# proiect.net
KiCad netlist of a schematic drawn in EAGLE
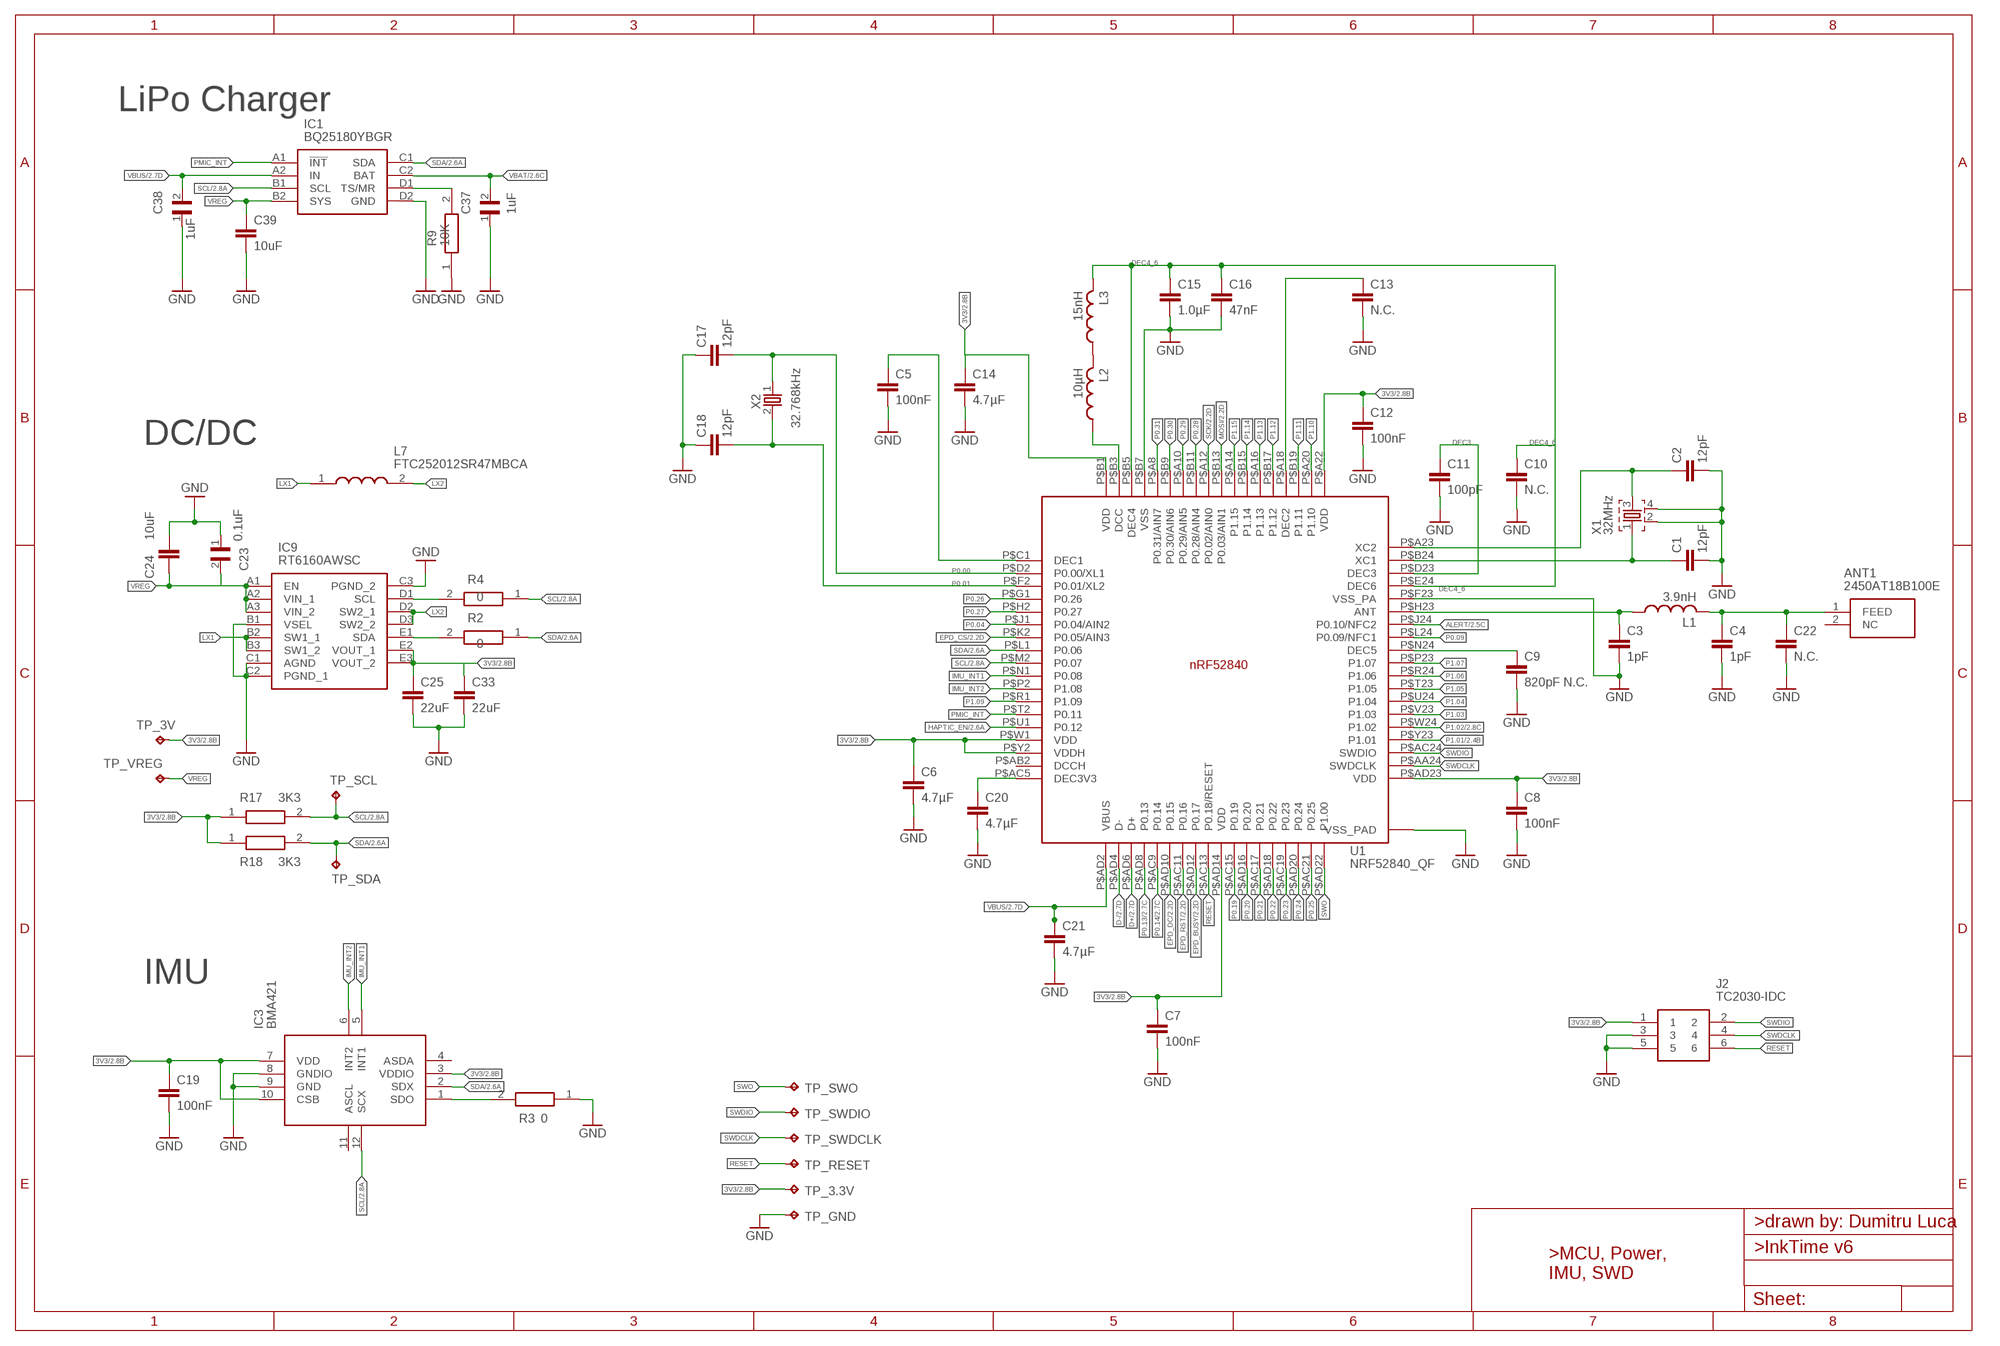
[diagram p0: schematic, sheet 1]
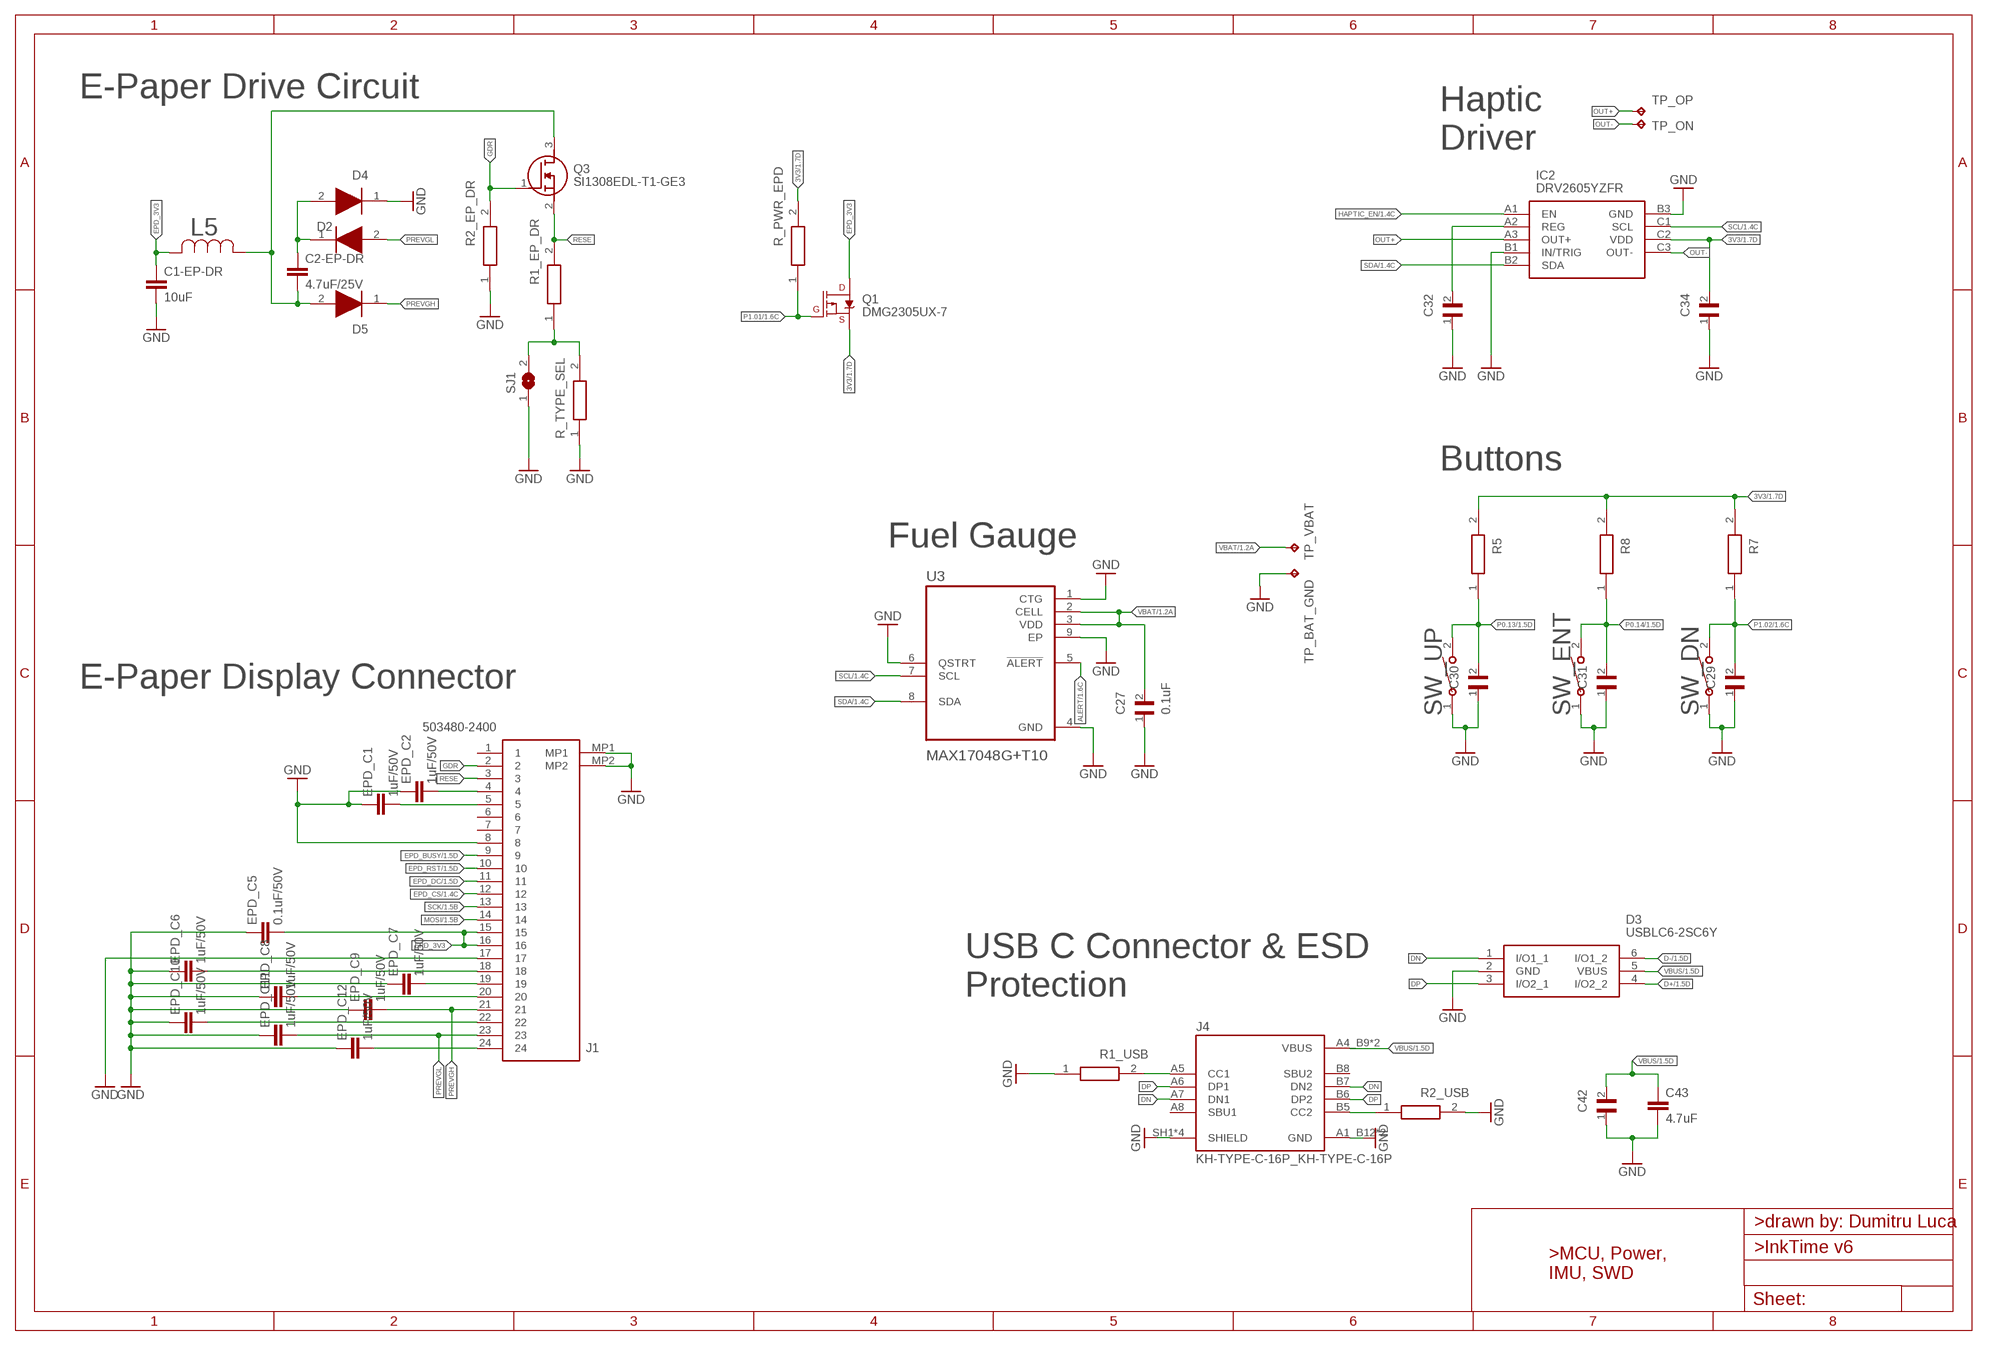
[diagram p1: schematic, sheet 2]

(export (version "E")
  (design (tool "Eeschema 10.0.6"))
  (components
    (comp (ref "ANT1")
      (value "2450AT18B100E")
      (footprint "eagle-import:2450AT18B100E_ANTC3216X140N")
      (fields (field (name "MOUSER_PART_NUMBER") "609-2450AT18B100E"))
      (libsource (lib "eagle-import") (part "2450AT18B100E_2450AT18B100E"))
    )
    (comp (ref "C1")
      (value "12pF")
      (footprint "eagle-import:NORDIC_NRF_3_RESC0201_L")
      (libsource (lib "eagle-import") (part "NORDIC_NRF_3_CAPACITOR_0201_L"))
    )
    (comp (ref "C2")
      (value "12pF")
      (footprint "eagle-import:NORDIC_NRF_3_RESC0201_L")
      (libsource (lib "eagle-import") (part "NORDIC_NRF_3_CAPACITOR_0201_L"))
    )
    (comp (ref "C3")
      (value "1pF")
      (footprint "eagle-import:NORDIC_NRF_3_RESC0201_L")
      (libsource (lib "eagle-import") (part "NORDIC_NRF_3_CAPACITOR_0201_L"))
    )
    (comp (ref "C4")
      (value "1pF")
      (footprint "eagle-import:NORDIC_NRF_3_RESC0201_L")
      (libsource (lib "eagle-import") (part "NORDIC_NRF_3_CAPACITOR_0201_L"))
    )
    (comp (ref "C5")
      (value "100nF")
      (footprint "eagle-import:NORDIC_NRF_3_RESC0201_L")
      (libsource (lib "eagle-import") (part "NORDIC_NRF_3_CAPACITOR_0201_L"))
    )
    (comp (ref "C6")
      (value "4.7µF")
      (footprint "eagle-import:NORDIC_NRF_3_RESC0201_L")
      (libsource (lib "eagle-import") (part "NORDIC_NRF_3_CAPACITOR_0201_L"))
    )
    (comp (ref "C7")
      (value "100nF")
      (footprint "eagle-import:NORDIC_NRF_3_RESC0201_L")
      (libsource (lib "eagle-import") (part "NORDIC_NRF_3_CAPACITOR_0201_L"))
    )
    (comp (ref "C8")
      (value "100nF")
      (footprint "eagle-import:NORDIC_NRF_3_RESC0201_L")
      (libsource (lib "eagle-import") (part "NORDIC_NRF_3_CAPACITOR_0201_L"))
    )
    (comp (ref "C9")
      (value "820pF N.C.")
      (footprint "eagle-import:NORDIC_NRF_3_RESC0201_L")
      (libsource (lib "eagle-import") (part "NORDIC_NRF_3_CAPACITOR_0201_L"))
    )
    (comp (ref "C10")
      (value "N.C.")
      (footprint "eagle-import:NORDIC_NRF_3_RESC0201_L")
      (libsource (lib "eagle-import") (part "NORDIC_NRF_3_CAPACITOR_0201_L"))
    )
    (comp (ref "C11")
      (value "100pF")
      (footprint "eagle-import:NORDIC_NRF_3_RESC0201_L")
      (libsource (lib "eagle-import") (part "NORDIC_NRF_3_CAPACITOR_0201_L"))
    )
    (comp (ref "C12")
      (value "100nF")
      (footprint "eagle-import:NORDIC_NRF_3_RESC0201_L")
      (libsource (lib "eagle-import") (part "NORDIC_NRF_3_CAPACITOR_0201_L"))
    )
    (comp (ref "C13")
      (value "N.C.")
      (footprint "eagle-import:NORDIC_NRF_3_RESC0201_L")
      (libsource (lib "eagle-import") (part "NORDIC_NRF_3_CAPACITOR_0201_L"))
    )
    (comp (ref "C14")
      (value "4.7µF")
      (footprint "eagle-import:NORDIC_NRF_3_RESC0201_L")
      (libsource (lib "eagle-import") (part "NORDIC_NRF_3_CAPACITOR_0201_L"))
    )
    (comp (ref "C15")
      (value "1.0µF")
      (footprint "eagle-import:NORDIC_NRF_3_RESC0201_L")
      (libsource (lib "eagle-import") (part "NORDIC_NRF_3_CAPACITOR_0201_L"))
    )
    (comp (ref "C16")
      (value "47nF")
      (footprint "eagle-import:NORDIC_NRF_3_RESC0201_L")
      (libsource (lib "eagle-import") (part "NORDIC_NRF_3_CAPACITOR_0201_L"))
    )
    (comp (ref "C17")
      (value "12pF")
      (footprint "eagle-import:NORDIC_NRF_3_RESC0201_L")
      (libsource (lib "eagle-import") (part "NORDIC_NRF_3_CAPACITOR_0201_L"))
    )
    (comp (ref "C18")
      (value "12pF")
      (footprint "eagle-import:NORDIC_NRF_3_RESC0201_L")
      (libsource (lib "eagle-import") (part "NORDIC_NRF_3_CAPACITOR_0201_L"))
    )
    (comp (ref "C19")
      (value "100nF")
      (footprint "eagle-import:NORDIC_NRF_3_RESC0201_L")
      (libsource (lib "eagle-import") (part "NORDIC_NRF_3_CAPACITOR_0201_L"))
    )
    (comp (ref "C20")
      (value "4.7µF")
      (footprint "eagle-import:NORDIC_NRF_3_RESC0201_L")
      (libsource (lib "eagle-import") (part "NORDIC_NRF_3_CAPACITOR_0201_L"))
    )
    (comp (ref "C21")
      (value "4.7µF")
      (footprint "eagle-import:NORDIC_NRF_3_RESC0201_L")
      (libsource (lib "eagle-import") (part "NORDIC_NRF_3_CAPACITOR_0201_L"))
    )
    (comp (ref "C22")
      (value "N.C.")
      (footprint "eagle-import:NORDIC_NRF_3_RESC0201_L")
      (libsource (lib "eagle-import") (part "NORDIC_NRF_3_CAPACITOR_0201_L"))
    )
    (comp (ref "C23")
      (value "0.1uF")
      (footprint "eagle-import:GRM011R60J152KE01L_1_0201")
      (libsource (lib "eagle-import") (part "GRM011R60J152KE01L_1_GRM011R60J152KE01L"))
    )
    (comp (ref "C24")
      (value "10uF")
      (footprint "eagle-import:NORDIC_NRF_3_RESC0201_L")
      (libsource (lib "eagle-import") (part "NORDIC_NRF_3_CAPACITOR_0201_L"))
    )
    (comp (ref "C25")
      (value "22uF")
      (footprint "eagle-import:NORDIC_NRF_3_RESC0201_L")
      (libsource (lib "eagle-import") (part "NORDIC_NRF_3_CAPACITOR_0201_L"))
    )
    (comp (ref "C33")
      (value "22uF")
      (footprint "eagle-import:NORDIC_NRF_3_RESC0201_L")
      (libsource (lib "eagle-import") (part "NORDIC_NRF_3_CAPACITOR_0201_L"))
    )
    (comp (ref "C37")
      (value "1uF")
      (footprint "eagle-import:GRM011R60J152KE01L_1_0201")
      (libsource (lib "eagle-import") (part "GRM011R60J152KE01L_1_GRM011R60J152KE01L"))
    )
    (comp (ref "C38")
      (value "1uF")
      (footprint "eagle-import:GRM011R60J152KE01L_1_0201")
      (libsource (lib "eagle-import") (part "GRM011R60J152KE01L_1_GRM011R60J152KE01L"))
    )
    (comp (ref "C39")
      (value "10uF")
      (footprint "eagle-import:NORDIC_NRF_3_RESC0201_L")
      (libsource (lib "eagle-import") (part "NORDIC_NRF_3_CAPACITOR_0201_L"))
    )
    (comp (ref "IC1")
      (value "BQ25180YBGR")
      (footprint "eagle-import:BQ25180YBGR_BGA8C40P2X4_100X155X50")
      (fields (field (name "MOUSER_PART_NUMBER") "595-BQ25180YBGR"))
      (libsource (lib "eagle-import") (part "BQ25180YBGR_BQ25180YBGR"))
    )
    (comp (ref "IC3")
      (value "BMA421")
      (footprint "eagle-import:BMA423_BMA423")
      (fields (field (name "ARROW_PART_NUMBER") "BMA423") (field (name "MOUSER_PART_NUMBER") "262-BMA423"))
      (libsource (lib "eagle-import") (part "BMA423_BMA423"))
    )
    (comp (ref "IC9")
      (value "RT6160AWSC")
      (footprint "eagle-import:RT6160AWSC_BGA15C40P3X5_140X230X60")
      (fields (field (name "MOUSER_PART_NUMBER") "835-RT6160AWSC"))
      (libsource (lib "eagle-import") (part "RT6160AWSC_RT6160AWSC"))
    )
    (comp (ref "J2")
      (value "TC2030-IDC")
      (footprint "eagle-import:TC2030-IDC_TC2030IDC")
      (libsource (lib "eagle-import") (part "TC2030-IDC_TC2030-IDC"))
    )
    (comp (ref "L1")
      (value "3.9nH")
      (footprint "eagle-import:NORDIC_NRF_2_RESC0402_L")
      (libsource (lib "eagle-import") (part "NORDIC_NRF_2_INDUCTOR_0402_L"))
    )
    (comp (ref "L2")
      (value "10µH")
      (footprint "eagle-import:NORDIC_NRF_2_RESC0402_L")
      (libsource (lib "eagle-import") (part "NORDIC_NRF_2_INDUCTOR_0402_L"))
    )
    (comp (ref "L3")
      (value "15nH")
      (footprint "eagle-import:NORDIC_NRF_2_RESC0402_L")
      (libsource (lib "eagle-import") (part "NORDIC_NRF_2_INDUCTOR_0402_L"))
    )
    (comp (ref "L7")
      (value "FTC252012SR47MBCA")
      (footprint "eagle-import:MLP2016SR47MT0S1_INDC2016X100N")
      (libsource (lib "eagle-import") (part "MLP2016SR47MT0S1_FTC252012SR47MBCA"))
    )
    (comp (ref "R2")
      (value "0")
      (footprint "eagle-import:CPF0201D7K68C1_0201")
      (libsource (lib "eagle-import") (part "CPF0201D7K68C1_CPF0201D7K68C1"))
    )
    (comp (ref "R3")
      (value "0")
      (footprint "eagle-import:CPF0201D7K68C1_0201")
      (libsource (lib "eagle-import") (part "CPF0201D7K68C1_CPF0201D7K68C1"))
    )
    (comp (ref "R4")
      (value "0")
      (footprint "eagle-import:CPF0201D7K68C1_0201")
      (libsource (lib "eagle-import") (part "CPF0201D7K68C1_CPF0201D7K68C1"))
    )
    (comp (ref "R9")
      (value "10K")
      (footprint "eagle-import:CPF0201D7K68C1_0201")
      (libsource (lib "eagle-import") (part "CPF0201D7K68C1_CPF0201D7K68C1"))
    )
    (comp (ref "R17")
      (value "3K3")
      (footprint "eagle-import:CPF0201D7K68C1_0201")
      (libsource (lib "eagle-import") (part "CPF0201D7K68C1_CPF0201D7K68C1"))
    )
    (comp (ref "R18")
      (value "3K3")
      (footprint "eagle-import:CPF0201D7K68C1_0201")
      (libsource (lib "eagle-import") (part "CPF0201D7K68C1_CPF0201D7K68C1"))
    )
    (comp (ref "TP_3.3V")
      (value "HECTOR_WATCH_1_TPTP20R")
      (footprint "eagle-import:HECTOR_WATCH_1_TP20R")
      (libsource (lib "eagle-import") (part "HECTOR_WATCH_1_TPTP20R"))
    )
    (comp (ref "TP_3V")
      (value "HECTOR_WATCH_1_TPTP20R")
      (footprint "eagle-import:HECTOR_WATCH_1_TP20R")
      (libsource (lib "eagle-import") (part "HECTOR_WATCH_1_TPTP20R"))
    )
    (comp (ref "TP_GND")
      (value "HECTOR_WATCH_1_TPTP20R")
      (footprint "eagle-import:HECTOR_WATCH_1_TP20R")
      (libsource (lib "eagle-import") (part "HECTOR_WATCH_1_TPTP20R"))
    )
    (comp (ref "TP_RESET")
      (value "HECTOR_WATCH_1_TPTP20R")
      (footprint "eagle-import:HECTOR_WATCH_1_TP20R")
      (libsource (lib "eagle-import") (part "HECTOR_WATCH_1_TPTP20R"))
    )
    (comp (ref "TP_SCL")
      (value "HECTOR_WATCH_1_TPTP20R")
      (footprint "eagle-import:HECTOR_WATCH_1_TP20R")
      (libsource (lib "eagle-import") (part "HECTOR_WATCH_1_TPTP20R"))
    )
    (comp (ref "TP_SDA")
      (value "HECTOR_WATCH_1_TPTP20R")
      (footprint "eagle-import:HECTOR_WATCH_1_TP20R")
      (libsource (lib "eagle-import") (part "HECTOR_WATCH_1_TPTP20R"))
    )
    (comp (ref "TP_SWDCLK")
      (value "HECTOR_WATCH_1_TPTP20R")
      (footprint "eagle-import:HECTOR_WATCH_1_TP20R")
      (libsource (lib "eagle-import") (part "HECTOR_WATCH_1_TPTP20R"))
    )
    (comp (ref "TP_SWDIO")
      (value "HECTOR_WATCH_1_TPTP20R")
      (footprint "eagle-import:HECTOR_WATCH_1_TP20R")
      (libsource (lib "eagle-import") (part "HECTOR_WATCH_1_TPTP20R"))
    )
    (comp (ref "TP_SWO")
      (value "HECTOR_WATCH_1_TPTP20R")
      (footprint "eagle-import:HECTOR_WATCH_1_TP20R")
      (libsource (lib "eagle-import") (part "HECTOR_WATCH_1_TPTP20R"))
    )
    (comp (ref "TP_VREG")
      (value "HECTOR_WATCH_1_TPTP20R")
      (footprint "eagle-import:HECTOR_WATCH_1_TP20R")
      (libsource (lib "eagle-import") (part "HECTOR_WATCH_1_TPTP20R"))
    )
    (comp (ref "U1")
      (value "NRF52840_QF")
      (footprint "eagle-import:NORDIC_NRF_4_AQFN50P700X700X85_HS-74N")
      (libsource (lib "eagle-import") (part "NORDIC_NRF_4_NRF52840_QF"))
    )
    (comp (ref "X1")
      (value "32MHz")
      (footprint "eagle-import:NORDIC_NRF_BT-XTAL_2016_N")
      (libsource (lib "eagle-import") (part "NORDIC_NRF_XTAL_32MHZ"))
    )
    (comp (ref "X2")
      (value "32.768kHz")
      (footprint "eagle-import:NORDIC_NRF_1_XTAL_3215_N")
      (libsource (lib "eagle-import") (part "NORDIC_NRF_1_XTAL_32KHZ"))
    )
    (comp (ref "C1-EP-DR")
      (value "10uF")
      (footprint "eagle-import:NORDIC_NRF_3_RESC0201_L")
      (libsource (lib "eagle-import") (part "NORDIC_NRF_3_CAPACITOR_0201_L"))
    )
    (comp (ref "C2-EP-DR")
      (value "4.7uF/25V")
      (footprint "eagle-import:NORDIC_NRF_3_RESC0201_L")
      (libsource (lib "eagle-import") (part "NORDIC_NRF_3_CAPACITOR_0201_L"))
    )
    (comp (ref "C27")
      (value "0.1uF")
      (footprint "eagle-import:GRM011R60J152KE01L_1_0201")
      (libsource (lib "eagle-import") (part "GRM011R60J152KE01L_1_GRM011R60J152KE01L"))
    )
    (comp (ref "C29")
      (value "1uF")
      (footprint "eagle-import:GRM011R60J152KE01L_1_0201")
      (libsource (lib "eagle-import") (part "GRM011R60J152KE01L_1_GRM011R60J152KE01L"))
    )
    (comp (ref "C30")
      (value "1uF")
      (footprint "eagle-import:GRM011R60J152KE01L_1_0201")
      (libsource (lib "eagle-import") (part "GRM011R60J152KE01L_1_GRM011R60J152KE01L"))
    )
    (comp (ref "C31")
      (value "1uF")
      (footprint "eagle-import:GRM011R60J152KE01L_1_0201")
      (libsource (lib "eagle-import") (part "GRM011R60J152KE01L_1_GRM011R60J152KE01L"))
    )
    (comp (ref "C32")
      (value "1uF")
      (footprint "eagle-import:GRM011R60J152KE01L_1_0201")
      (libsource (lib "eagle-import") (part "GRM011R60J152KE01L_1_GRM011R60J152KE01L"))
    )
    (comp (ref "C34")
      (value "0.1uF")
      (footprint "eagle-import:GRM011R60J152KE01L_1_0201")
      (libsource (lib "eagle-import") (part "GRM011R60J152KE01L_1_GRM011R60J152KE01L"))
    )
    (comp (ref "C42")
      (value "0.1uF")
      (footprint "eagle-import:GRM011R60J152KE01L_1_0201")
      (libsource (lib "eagle-import") (part "GRM011R60J152KE01L_1_GRM011R60J152KE01L"))
    )
    (comp (ref "C43")
      (value "4.7uF")
      (footprint "eagle-import:NORDIC_NRF_3_RESC0201_L")
      (libsource (lib "eagle-import") (part "NORDIC_NRF_3_CAPACITOR_0201_L"))
    )
    (comp (ref "D2")
      (value "ESP32_C6_LIBRARY_5_MBR0530")
      (footprint "eagle-import:ESP32_C6_LIBRARY_5_SOD3716X135N")
      (fields (field (name "MF") "ON Semiconductor") (field (name "MP") "MBR0530"))
      (libsource (lib "eagle-import") (part "ESP32_C6_LIBRARY_5_MBR0530"))
    )
    (comp (ref "D3")
      (value "USBLC6-2SC6Y")
      (footprint "eagle-import:ESP32_C6_LIBRARY_3_SOT95P280X145-6N")
      (fields (field (name "MF") "STMicroelectronics"))
      (libsource (lib "eagle-import") (part "ESP32_C6_LIBRARY_3_USBLC6-2SC6Y"))
    )
    (comp (ref "D4")
      (value "ESP32_C6_LIBRARY_5_MBR0530")
      (footprint "eagle-import:ESP32_C6_LIBRARY_5_SOD3716X135N")
      (fields (field (name "MF") "ON Semiconductor") (field (name "MP") "MBR0530"))
      (libsource (lib "eagle-import") (part "ESP32_C6_LIBRARY_5_MBR0530"))
    )
    (comp (ref "D5")
      (value "ESP32_C6_LIBRARY_5_MBR0530")
      (footprint "eagle-import:ESP32_C6_LIBRARY_5_SOD3716X135N")
      (fields (field (name "MF") "ON Semiconductor") (field (name "MP") "MBR0530"))
      (libsource (lib "eagle-import") (part "ESP32_C6_LIBRARY_5_MBR0530"))
    )
    (comp (ref "EPD_C1")
      (value "1uF/50V")
      (footprint "eagle-import:NORDIC_NRF_3_RESC0201_L")
      (libsource (lib "eagle-import") (part "NORDIC_NRF_3_CAPACITOR_0201_L"))
    )
    (comp (ref "EPD_C2")
      (value "1uF/50V")
      (footprint "eagle-import:NORDIC_NRF_3_RESC0201_L")
      (libsource (lib "eagle-import") (part "NORDIC_NRF_3_CAPACITOR_0201_L"))
    )
    (comp (ref "EPD_C5")
      (value "0.1uF/50V")
      (footprint "eagle-import:NORDIC_NRF_3_RESC0201_L")
      (libsource (lib "eagle-import") (part "NORDIC_NRF_3_CAPACITOR_0201_L"))
    )
    (comp (ref "EPD_C6")
      (value "1uF/50V")
      (footprint "eagle-import:NORDIC_NRF_3_RESC0201_L")
      (libsource (lib "eagle-import") (part "NORDIC_NRF_3_CAPACITOR_0201_L"))
    )
    (comp (ref "EPD_C7")
      (value "1uF/50V")
      (footprint "eagle-import:NORDIC_NRF_3_RESC0201_L")
      (libsource (lib "eagle-import") (part "NORDIC_NRF_3_CAPACITOR_0201_L"))
    )
    (comp (ref "EPD_C8")
      (value "1uF/50V")
      (footprint "eagle-import:NORDIC_NRF_3_RESC0201_L")
      (libsource (lib "eagle-import") (part "NORDIC_NRF_3_CAPACITOR_0201_L"))
    )
    (comp (ref "EPD_C9")
      (value "1uF/50V")
      (footprint "eagle-import:NORDIC_NRF_3_RESC0201_L")
      (libsource (lib "eagle-import") (part "NORDIC_NRF_3_CAPACITOR_0201_L"))
    )
    (comp (ref "EPD_C10")
      (value "1uF/50V")
      (footprint "eagle-import:NORDIC_NRF_3_RESC0201_L")
      (libsource (lib "eagle-import") (part "NORDIC_NRF_3_CAPACITOR_0201_L"))
    )
    (comp (ref "EPD_C11")
      (value "1uF/50V")
      (footprint "eagle-import:NORDIC_NRF_3_RESC0201_L")
      (libsource (lib "eagle-import") (part "NORDIC_NRF_3_CAPACITOR_0201_L"))
    )
    (comp (ref "EPD_C12")
      (value "1uF/50V")
      (footprint "eagle-import:NORDIC_NRF_3_RESC0201_L")
      (libsource (lib "eagle-import") (part "NORDIC_NRF_3_CAPACITOR_0201_L"))
    )
    (comp (ref "IC2")
      (value "DRV2605YZFR")
      (footprint "eagle-import:DRV2605YZFR_BGA9C50P3X3_144X144X62")
      (libsource (lib "eagle-import") (part "DRV2605YZFR_DRV2605YZFR"))
    )
    (comp (ref "J1")
      (value "503480-2400")
      (footprint "eagle-import:503480-2400_5034802400")
      (fields (field (name "MOUSER_PART_NUMBER") "538-503480-2400"))
      (libsource (lib "eagle-import") (part "503480-2400_503480-2400"))
    )
    (comp (ref "J4")
      (value "KH-TYPE-C-16P_KH-TYPE-C-16P")
      (footprint "eagle-import:KH-TYPE-C-16P_KINGHELM_KH-TYPE-C-16P")
      (fields (field (name "MF") "kinghelm") (field (name "MP") "KH-TYPE-C-16P"))
      (libsource (lib "eagle-import") (part "KH-TYPE-C-16P_KH-TYPE-C-16P"))
    )
    (comp (ref "L5")
      (value "ESP32_C6_LIBRARY_2_744043680IND_4828-WE-TPC_WRE")
      (footprint "eagle-import:ESP32_C6_LIBRARY_2_IND_4828-WE-TPC_WRE")
      (fields
        (field (name "MANUFACTURER_PART_NUMBER") "744043680")
        (field (name "COPYRIGHT") "Copyright (C) 2024 Ultra Librarian. All rights reserved.")
      )
      (libsource (lib "eagle-import") (part "ESP32_C6_LIBRARY_2_744043680IND_4828-WE-TPC_WRE"))
    )
    (comp (ref "Q1")
      (value "DMG2305UX-7")
      (footprint "eagle-import:ESP32_C6_LIBRARY_4_ESP32_C6_LIBRARY_4_ESP32_C6_LIBRARY_4_ESP32_C6_LIBRARY_4_ESP32_WROVER_SPARKFUN-DISCRETESEMI_SOT23-3")
      (libsource (lib "eagle-import") (part "ESP32_C6_LIBRARY_4_ESP32_WROVER_SPARKFUN-DISCRETESEMI_MOSFET_PCH-DMG2305UX-7"))
    )
    (comp (ref "Q3")
      (value "SI1308EDL-T1-GE3")
      (footprint "eagle-import:ESP32_C6_LIBRARY_6_SOT65P210X110-3N")
      (fields (field (name "MF") "Vishay Siliconix"))
      (libsource (lib "eagle-import") (part "ESP32_C6_LIBRARY_6_SI1308EDL-T1-GE3"))
    )
    (comp (ref "R1_EP_DR")
      (value "0.47")
      (footprint "eagle-import:CPF0201D7K68C1_0201")
      (libsource (lib "eagle-import") (part "CPF0201D7K68C1_CPF0201D7K68C1"))
    )
    (comp (ref "R1_USB")
      (value "5K1")
      (footprint "eagle-import:CPF0201D7K68C1_0201")
      (libsource (lib "eagle-import") (part "CPF0201D7K68C1_CPF0201D7K68C1"))
    )
    (comp (ref "R2_EP_DR")
      (value "10K")
      (footprint "eagle-import:CPF0201D7K68C1_0201")
      (libsource (lib "eagle-import") (part "CPF0201D7K68C1_CPF0201D7K68C1"))
    )
    (comp (ref "R2_USB")
      (value "5K1")
      (footprint "eagle-import:CPF0201D7K68C1_0201")
      (libsource (lib "eagle-import") (part "CPF0201D7K68C1_CPF0201D7K68C1"))
    )
    (comp (ref "R5")
      (value "10K")
      (footprint "eagle-import:CPF0201D7K68C1_0201")
      (libsource (lib "eagle-import") (part "CPF0201D7K68C1_CPF0201D7K68C1"))
    )
    (comp (ref "R7")
      (value "10K")
      (footprint "eagle-import:CPF0201D7K68C1_0201")
      (libsource (lib "eagle-import") (part "CPF0201D7K68C1_CPF0201D7K68C1"))
    )
    (comp (ref "R8")
      (value "10K")
      (footprint "eagle-import:CPF0201D7K68C1_0201")
      (libsource (lib "eagle-import") (part "CPF0201D7K68C1_CPF0201D7K68C1"))
    )
    (comp (ref "R_PWR_EPD")
      (value "10K")
      (footprint "eagle-import:CPF0201D7K68C1_0201")
      (libsource (lib "eagle-import") (part "CPF0201D7K68C1_CPF0201D7K68C1"))
    )
    (comp (ref "R_TYPE_SEL")
      (value "2.2")
      (footprint "eagle-import:CPF0201D7K68C1_0201")
      (libsource (lib "eagle-import") (part "CPF0201D7K68C1_CPF0201D7K68C1"))
    )
    (comp (ref "SJ1")
      (value "ESP32_C6_LIBRARY_7_JUMPER_SJ")
      (footprint "eagle-import:ESP32_C6_LIBRARY_7_JUMPER_SJ")
      (libsource (lib "eagle-import") (part "ESP32_C6_LIBRARY_7_JUMPER_SJ"))
    )
    (comp (ref "SW_DN")
      (value "2025-10-22_07-23-44_LIBRARY_EVP-AKE31ASW_EVP-AKE31A_PAN")
      (footprint "eagle-import:2025-10-22_07-23-44_LIBRARY_SW_EVP-AKE31A_PAN")
      (fields
        (field (name "MANUFACTURER_PART_NUMBER") "EVP-AKE31A")
        (field (name "COPYRIGHT") "Copyright (C) 2025 Ultra Librarian. All rights reserved.")
      )
      (libsource (lib "eagle-import") (part "2025-10-22_07-23-44_LIBRARY_EVP-AKE31ASW_EVP-AKE31A_PAN"))
    )
    (comp (ref "SW_ENT")
      (value "2025-10-22_07-23-44_LIBRARY_EVP-AKE31ASW_EVP-AKE31A_PAN")
      (footprint "eagle-import:2025-10-22_07-23-44_LIBRARY_SW_EVP-AKE31A_PAN")
      (fields
        (field (name "MANUFACTURER_PART_NUMBER") "EVP-AKE31A")
        (field (name "COPYRIGHT") "Copyright (C) 2025 Ultra Librarian. All rights reserved.")
      )
      (libsource (lib "eagle-import") (part "2025-10-22_07-23-44_LIBRARY_EVP-AKE31ASW_EVP-AKE31A_PAN"))
    )
    (comp (ref "SW_UP")
      (value "2025-10-22_07-23-44_LIBRARY_EVP-AKE31ASW_EVP-AKE31A_PAN")
      (footprint "eagle-import:2025-10-22_07-23-44_LIBRARY_SW_EVP-AKE31A_PAN")
      (fields
        (field (name "MANUFACTURER_PART_NUMBER") "EVP-AKE31A")
        (field (name "COPYRIGHT") "Copyright (C) 2025 Ultra Librarian. All rights reserved.")
      )
      (libsource (lib "eagle-import") (part "2025-10-22_07-23-44_LIBRARY_EVP-AKE31ASW_EVP-AKE31A_PAN"))
    )
    (comp (ref "TP_BAT_GND")
      (value "HECTOR_WATCH_1_TPTP20R")
      (footprint "eagle-import:HECTOR_WATCH_1_TP20R")
      (libsource (lib "eagle-import") (part "HECTOR_WATCH_1_TPTP20R"))
    )
    (comp (ref "TP_ON")
      (value "HECTOR_WATCH_1_TPTP20R")
      (footprint "eagle-import:HECTOR_WATCH_1_TP20R")
      (libsource (lib "eagle-import") (part "HECTOR_WATCH_1_TPTP20R"))
    )
    (comp (ref "TP_OP")
      (value "HECTOR_WATCH_1_TPTP20R")
      (footprint "eagle-import:HECTOR_WATCH_1_TP20R")
      (libsource (lib "eagle-import") (part "HECTOR_WATCH_1_TPTP20R"))
    )
    (comp (ref "TP_VBAT")
      (value "HECTOR_WATCH_1_TPTP20R")
      (footprint "eagle-import:HECTOR_WATCH_1_TP20R")
      (libsource (lib "eagle-import") (part "HECTOR_WATCH_1_TPTP20R"))
    )
    (comp (ref "U3")
      (value "MAX17048G+T10")
      (footprint "eagle-import:ESP32_C6_LIBRARY_SON50P200X200X80-9N")
      (fields (field (name "MF") "Analog Devices"))
      (libsource (lib "eagle-import") (part "ESP32_C6_LIBRARY_MAX17048G+T10"))
    )
  )
  (nets
    (net (code "1") (name "3V3") (class "Default")
      (node (ref "C12") (pin "1") (pinfunction "1_1") (pintype "passive"))
      (node (ref "C14") (pin "1") (pinfunction "1_1") (pintype "passive"))
      (node (ref "C19") (pin "1") (pinfunction "1_1") (pintype "passive"))
      (node (ref "C25") (pin "1") (pinfunction "1_1") (pintype "passive"))
      (node (ref "C34") (pin "2") (pinfunction "2_2") (pintype "passive"))
      (node (ref "C6") (pin "1") (pinfunction "1_1") (pintype "passive"))
      (node (ref "C7") (pin "1") (pinfunction "1_1") (pintype "passive"))
      (node (ref "C8") (pin "1") (pinfunction "1_1") (pintype "passive"))
      (node (ref "IC2") (pin "C2") (pinfunction "VDD_C2") (pintype "bidirectional"))
      (node (ref "IC3") (pin "10") (pinfunction "CSB_10") (pintype "bidirectional"))
      (node (ref "IC3") (pin "3") (pinfunction "VDDIO_3") (pintype "bidirectional"))
      (node (ref "IC3") (pin "7") (pinfunction "VDD_7") (pintype "bidirectional"))
      (node (ref "IC9") (pin "E2") (pinfunction "VOUT_1_E2") (pintype "bidirectional"))
      (node (ref "IC9") (pin "E3") (pinfunction "VOUT_2_E3") (pintype "bidirectional"))
      (node (ref "J2") (pin "1") (pinfunction "1_1") (pintype "bidirectional"))
      (node (ref "Q1") (pin "2") (pinfunction "S_2") (pintype "bidirectional"))
      (node (ref "R17") (pin "1") (pinfunction "1_1") (pintype "bidirectional"))
      (node (ref "R18") (pin "1") (pinfunction "1_1") (pintype "bidirectional"))
      (node (ref "R5") (pin "2") (pinfunction "2_2") (pintype "bidirectional"))
      (node (ref "R7") (pin "2") (pinfunction "2_2") (pintype "bidirectional"))
      (node (ref "R8") (pin "2") (pinfunction "2_2") (pintype "bidirectional"))
      (node (ref "R_PWR_EPD") (pin "2") (pinfunction "2_2") (pintype "bidirectional"))
      (node (ref "TP_3.3V") (pin "TP") (pinfunction "TP_TP") (pintype "input"))
      (node (ref "TP_3V") (pin "TP") (pinfunction "TP_TP") (pintype "input"))
      (node (ref "U1") (pin "P$A22") (pinfunction "VDD_P$A22") (pintype "power_in"))
      (node (ref "U1") (pin "P$AD14") (pinfunction "VDD_P$AD14") (pintype "power_in"))
      (node (ref "U1") (pin "P$AD23") (pinfunction "VDD_P$AD23") (pintype "power_in"))
      (node (ref "U1") (pin "P$B1") (pinfunction "VDD_P$B1") (pintype "power_in"))
      (node (ref "U1") (pin "P$W1") (pinfunction "VDD_P$W1") (pintype "power_in"))
      (node (ref "U1") (pin "P$Y2") (pinfunction "VDDH_P$Y2") (pintype "power_in"))
    )
    (net (code "2") (name "ALERT") (class "Default")
      (node (ref "U1") (pin "P$J24") (pinfunction "P0.10/NFC2_P$J24") (pintype "bidirectional"))
      (node (ref "U3") (pin "5") (pinfunction "~{ALERT}_5") (pintype "output"))
    )
    (net (code "3") (name "D+") (class "Default")
      (node (ref "D3") (pin "4") (pinfunction "I/O2_2_4") (pintype "bidirectional"))
      (node (ref "U1") (pin "P$AD6") (pinfunction "D+_P$AD6") (pintype "bidirectional"))
    )
    (net (code "4") (name "D-") (class "Default")
      (node (ref "D3") (pin "6") (pinfunction "I/O1_2_6") (pintype "bidirectional"))
      (node (ref "U1") (pin "P$AD4") (pinfunction "D-_P$AD4") (pintype "bidirectional"))
    )
    (net (code "5") (name "DEC3") (class "Default")
      (node (ref "C11") (pin "1") (pinfunction "1_1") (pintype "passive"))
      (node (ref "U1") (pin "P$D23") (pinfunction "DEC3_P$D23") (pintype "bidirectional"))
    )
    (net (code "6") (name "DEC4_6") (class "Default")
      (node (ref "C10") (pin "1") (pinfunction "1_1") (pintype "passive"))
      (node (ref "C15") (pin "1") (pinfunction "1_1") (pintype "passive"))
      (node (ref "C16") (pin "1") (pinfunction "1_1") (pintype "passive"))
      (node (ref "L3") (pin "2") (pinfunction "2_2") (pintype "passive"))
      (node (ref "U1") (pin "P$B5") (pinfunction "DEC4_P$B5") (pintype "power_in"))
      (node (ref "U1") (pin "P$E24") (pinfunction "DEC6_P$E24") (pintype "bidirectional"))
    )
    (net (code "7") (name "DN") (class "Default")
      (node (ref "D3") (pin "1") (pinfunction "I/O1_1_1") (pintype "bidirectional"))
      (node (ref "J4") (pin "A7") (pinfunction "DN1_A7") (pintype "bidirectional"))
      (node (ref "J4") (pin "B7") (pinfunction "DN2_B7") (pintype "bidirectional"))
    )
    (net (code "8") (name "DP") (class "Default")
      (node (ref "D3") (pin "3") (pinfunction "I/O2_1_3") (pintype "bidirectional"))
      (node (ref "J4") (pin "A6") (pinfunction "DP1_A6") (pintype "bidirectional"))
      (node (ref "J4") (pin "B6") (pinfunction "DP2_B6") (pintype "bidirectional"))
    )
    (net (code "9") (name "EPD_3V3") (class "Default")
      (node (ref "C1-EP-DR") (pin "1") (pinfunction "1_1") (pintype "passive"))
      (node (ref "EPD_C5") (pin "2") (pinfunction "2_2") (pintype "passive"))
      (node (ref "J1") (pin "15") (pinfunction "15_15") (pintype "bidirectional"))
      (node (ref "J1") (pin "16") (pinfunction "16_16") (pintype "bidirectional"))
      (node (ref "L5") (pin "2") (pinfunction "2_2") (pintype "passive"))
      (node (ref "Q1") (pin "3") (pinfunction "D_3") (pintype "bidirectional"))
    )
    (net (code "10") (name "EPD_BUSY") (class "Default")
      (node (ref "J1") (pin "9") (pinfunction "9_9") (pintype "bidirectional"))
      (node (ref "U1") (pin "P$AD12") (pinfunction "P0.17_P$AD12") (pintype "bidirectional"))
    )
    (net (code "11") (name "EPD_CS") (class "Default")
      (node (ref "J1") (pin "12") (pinfunction "12_12") (pintype "bidirectional"))
      (node (ref "U1") (pin "P$K2") (pinfunction "P0.05/AIN3_P$K2") (pintype "bidirectional"))
    )
    (net (code "12") (name "EPD_DC") (class "Default")
      (node (ref "J1") (pin "11") (pinfunction "11_11") (pintype "bidirectional"))
      (node (ref "U1") (pin "P$AD10") (pinfunction "P0.15_P$AD10") (pintype "bidirectional"))
    )
    (net (code "13") (name "EPD_RST") (class "Default")
      (node (ref "J1") (pin "10") (pinfunction "10_10") (pintype "bidirectional"))
      (node (ref "U1") (pin "P$AC11") (pinfunction "P0.16_P$AC11") (pintype "bidirectional"))
    )
    (net (code "14") (name "GDR") (class "Default")
      (node (ref "J1") (pin "2") (pinfunction "2_2") (pintype "bidirectional"))
      (node (ref "Q3") (pin "1") (pinfunction "G_1") (pintype "bidirectional"))
      (node (ref "R2_EP_DR") (pin "2") (pinfunction "2_2") (pintype "bidirectional"))
    )
    (net (code "15") (name "GND") (class "Default")
      (node (ref "C1") (pin "2") (pinfunction "2_2") (pintype "passive"))
      (node (ref "C1-EP-DR") (pin "2") (pinfunction "2_2") (pintype "passive"))
      (node (ref "C10") (pin "2") (pinfunction "2_2") (pintype "passive"))
      (node (ref "C11") (pin "2") (pinfunction "2_2") (pintype "passive"))
      (node (ref "C12") (pin "2") (pinfunction "2_2") (pintype "passive"))
      (node (ref "C13") (pin "2") (pinfunction "2_2") (pintype "passive"))
      (node (ref "C14") (pin "2") (pinfunction "2_2") (pintype "passive"))
      (node (ref "C15") (pin "2") (pinfunction "2_2") (pintype "passive"))
      (node (ref "C16") (pin "2") (pinfunction "2_2") (pintype "passive"))
      (node (ref "C17") (pin "1") (pinfunction "1_1") (pintype "passive"))
      (node (ref "C18") (pin "1") (pinfunction "1_1") (pintype "passive"))
      (node (ref "C19") (pin "2") (pinfunction "2_2") (pintype "passive"))
      (node (ref "C2") (pin "2") (pinfunction "2_2") (pintype "passive"))
      (node (ref "C20") (pin "2") (pinfunction "2_2") (pintype "passive"))
      (node (ref "C21") (pin "2") (pinfunction "2_2") (pintype "passive"))
      (node (ref "C22") (pin "2") (pinfunction "2_2") (pintype "passive"))
      (node (ref "C23") (pin "1") (pinfunction "1_1") (pintype "passive"))
      (node (ref "C24") (pin "1") (pinfunction "1_1") (pintype "passive"))
      (node (ref "C25") (pin "2") (pinfunction "2_2") (pintype "passive"))
      (node (ref "C27") (pin "1") (pinfunction "1_1") (pintype "passive"))
      (node (ref "C29") (pin "1") (pinfunction "1_1") (pintype "passive"))
      (node (ref "C3") (pin "2") (pinfunction "2_2") (pintype "passive"))
      (node (ref "C30") (pin "1") (pinfunction "1_1") (pintype "passive"))
      (node (ref "C31") (pin "1") (pinfunction "1_1") (pintype "passive"))
      (node (ref "C32") (pin "1") (pinfunction "1_1") (pintype "passive"))
      (node (ref "C33") (pin "2") (pinfunction "2_2") (pintype "passive"))
      (node (ref "C34") (pin "1") (pinfunction "1_1") (pintype "passive"))
      (node (ref "C37") (pin "1") (pinfunction "1_1") (pintype "passive"))
      (node (ref "C38") (pin "1") (pinfunction "1_1") (pintype "passive"))
      (node (ref "C39") (pin "2") (pinfunction "2_2") (pintype "passive"))
      (node (ref "C4") (pin "2") (pinfunction "2_2") (pintype "passive"))
      (node (ref "C42") (pin "1") (pinfunction "1_1") (pintype "passive"))
      (node (ref "C43") (pin "2") (pinfunction "2_2") (pintype "passive"))
      (node (ref "C5") (pin "2") (pinfunction "2_2") (pintype "passive"))
      (node (ref "C6") (pin "2") (pinfunction "2_2") (pintype "passive"))
      (node (ref "C7") (pin "2") (pinfunction "2_2") (pintype "passive"))
      (node (ref "C8") (pin "2") (pinfunction "2_2") (pintype "passive"))
      (node (ref "C9") (pin "2") (pinfunction "2_2") (pintype "passive"))
      (node (ref "D3") (pin "2") (pinfunction "GND_2") (pintype "bidirectional"))
      (node (ref "D4") (pin "1") (pinfunction "K_1") (pintype "bidirectional"))
      (node (ref "EPD_C1") (pin "1") (pinfunction "1_1") (pintype "passive"))
      (node (ref "EPD_C10") (pin "1") (pinfunction "1_1") (pintype "passive"))
      (node (ref "EPD_C11") (pin "1") (pinfunction "1_1") (pintype "passive"))
      (node (ref "EPD_C12") (pin "1") (pinfunction "1_1") (pintype "passive"))
      (node (ref "EPD_C2") (pin "1") (pinfunction "1_1") (pintype "passive"))
      (node (ref "EPD_C5") (pin "1") (pinfunction "1_1") (pintype "passive"))
      (node (ref "EPD_C6") (pin "1") (pinfunction "1_1") (pintype "passive"))
      (node (ref "EPD_C7") (pin "1") (pinfunction "1_1") (pintype "passive"))
      (node (ref "EPD_C8") (pin "1") (pinfunction "1_1") (pintype "passive"))
      (node (ref "EPD_C9") (pin "1") (pinfunction "1_1") (pintype "passive"))
      (node (ref "IC1") (pin "D2") (pinfunction "GND_D2") (pintype "bidirectional"))
      (node (ref "IC2") (pin "B1") (pinfunction "IN/TRIG_B1") (pintype "bidirectional"))
      (node (ref "IC2") (pin "B3") (pinfunction "GND_B3") (pintype "bidirectional"))
      (node (ref "IC3") (pin "8") (pinfunction "GNDIO_8") (pintype "bidirectional"))
      (node (ref "IC3") (pin "9") (pinfunction "GND_9") (pintype "bidirectional"))
      (node (ref "IC9") (pin "B1") (pinfunction "VSEL_B1") (pintype "bidirectional"))
      (node (ref "IC9") (pin "C1") (pinfunction "AGND_C1") (pintype "bidirectional"))
      (node (ref "IC9") (pin "C2") (pinfunction "PGND_1_C2") (pintype "bidirectional"))
      (node (ref "IC9") (pin "C3") (pinfunction "PGND_2_C3") (pintype "bidirectional"))
      (node (ref "J1") (pin "17") (pinfunction "17_17") (pintype "bidirectional"))
      (node (ref "J1") (pin "8") (pinfunction "8_8") (pintype "bidirectional"))
      (node (ref "J1") (pin "MP1") (pinfunction "MP1_MP1") (pintype "bidirectional"))
      (node (ref "J1") (pin "MP2") (pinfunction "MP2_MP2") (pintype "bidirectional"))
      (node (ref "J2") (pin "3") (pinfunction "3_3") (pintype "bidirectional"))
      (node (ref "J2") (pin "5") (pinfunction "5_5") (pintype "bidirectional"))
      (node (ref "J4") (pin "A12_B1") (pinfunction "GND_A12_B1") (pintype "power_in"))
      (node (ref "J4") (pin "A1_B12") (pinfunction "GND_A1_B12") (pintype "power_in"))
      (node (ref "J4") (pin "SH1") (pinfunction "SHIELD_SH1") (pintype "passive"))
      (node (ref "J4") (pin "SH2") (pinfunction "SHIELD_SH2") (pintype "passive"))
      (node (ref "J4") (pin "SH3") (pinfunction "SHIELD_SH3") (pintype "passive"))
      (node (ref "J4") (pin "SH4") (pinfunction "SHIELD_SH4") (pintype "passive"))
      (node (ref "R1_USB") (pin "1") (pinfunction "1_1") (pintype "bidirectional"))
      (node (ref "R2_EP_DR") (pin "1") (pinfunction "1_1") (pintype "bidirectional"))
      (node (ref "R2_USB") (pin "2") (pinfunction "2_2") (pintype "bidirectional"))
      (node (ref "R3") (pin "1") (pinfunction "1_1") (pintype "bidirectional"))
      (node (ref "R9") (pin "1") (pinfunction "1_1") (pintype "bidirectional"))
      (node (ref "R_TYPE_SEL") (pin "1") (pinfunction "1_1") (pintype "bidirectional"))
      (node (ref "SJ1") (pin "1") (pinfunction "1_1") (pintype "passive"))
      (node (ref "SW_DN") (pin "1") (pinfunction "1_1") (pintype "passive"))
      (node (ref "SW_ENT") (pin "1") (pinfunction "1_1") (pintype "passive"))
      (node (ref "SW_UP") (pin "1") (pinfunction "1_1") (pintype "passive"))
      (node (ref "TP_BAT_GND") (pin "TP") (pinfunction "TP_TP") (pintype "input"))
      (node (ref "TP_GND") (pin "TP") (pinfunction "TP_TP") (pintype "input"))
      (node (ref "U1") (pin "P$74") (pinfunction "VSS_PAD_P$74") (pintype "bidirectional"))
      (node (ref "U1") (pin "P$75") (pinfunction "VSS_PAD_P$75") (pintype "bidirectional"))
      (node (ref "U1") (pin "P$76") (pinfunction "VSS_PAD_P$76") (pintype "bidirectional"))
      (node (ref "U1") (pin "P$77") (pinfunction "VSS_PAD_P$77") (pintype "bidirectional"))
      (node (ref "U1") (pin "P$78") (pinfunction "VSS_PAD_P$78") (pintype "bidirectional"))
      (node (ref "U1") (pin "P$79") (pinfunction "VSS_PAD_P$79") (pintype "bidirectional"))
      (node (ref "U1") (pin "P$80") (pinfunction "VSS_PAD_P$80") (pintype "bidirectional"))
      (node (ref "U1") (pin "P$81") (pinfunction "VSS_PAD_P$81") (pintype "bidirectional"))
      (node (ref "U1") (pin "P$82") (pinfunction "VSS_PAD_P$82") (pintype "bidirectional"))
      (node (ref "U1") (pin "P$83") (pinfunction "VSS_PAD_P$83") (pintype "bidirectional"))
      (node (ref "U1") (pin "P$84") (pinfunction "VSS_PAD_P$84") (pintype "bidirectional"))
      (node (ref "U1") (pin "P$85") (pinfunction "VSS_PAD_P$85") (pintype "bidirectional"))
      (node (ref "U1") (pin "P$86") (pinfunction "VSS_PAD_P$86") (pintype "bidirectional"))
      (node (ref "U1") (pin "P$87") (pinfunction "VSS_PAD_P$87") (pintype "bidirectional"))
      (node (ref "U1") (pin "P$88") (pinfunction "VSS_PAD_P$88") (pintype "bidirectional"))
      (node (ref "U1") (pin "P$89") (pinfunction "VSS_PAD_P$89") (pintype "bidirectional"))
      (node (ref "U1") (pin "P$90") (pinfunction "VSS_PAD_P$90") (pintype "bidirectional"))
      (node (ref "U1") (pin "P$B7") (pinfunction "VSS_P$B7") (pintype "power_in"))
      (node (ref "U1") (pin "P$F23") (pinfunction "VSS_PA_P$F23") (pintype "bidirectional"))
      (node (ref "U3") (pin "1") (pinfunction "CTG_1") (pintype "power_in"))
      (node (ref "U3") (pin "4") (pinfunction "GND_4") (pintype "power_in"))
      (node (ref "U3") (pin "6") (pinfunction "QSTRT_6") (pintype "input"))
      (node (ref "U3") (pin "9") (pinfunction "EP_9") (pintype "power_in"))
      (node (ref "X1") (pin "2") (pinfunction "2_2") (pintype "passive"))
      (node (ref "X1") (pin "4") (pinfunction "4_4") (pintype "passive"))
    )
    (net (code "16") (name "HAPTIC_EN") (class "Default")
      (node (ref "IC2") (pin "A1") (pinfunction "EN_A1") (pintype "bidirectional"))
      (node (ref "U1") (pin "P$U1") (pinfunction "P0.12_P$U1") (pintype "bidirectional"))
    )
    (net (code "17") (name "IMU_INT1") (class "Default")
      (node (ref "IC3") (pin "5") (pinfunction "INT1_5") (pintype "bidirectional"))
      (node (ref "U1") (pin "P$N1") (pinfunction "P0.08_P$N1") (pintype "bidirectional"))
    )
    (net (code "18") (name "IMU_INT2") (class "Default")
      (node (ref "IC3") (pin "6") (pinfunction "INT2_6") (pintype "bidirectional"))
      (node (ref "U1") (pin "P$P2") (pinfunction "P1.08_P$P2") (pintype "bidirectional"))
    )
    (net (code "19") (name "LX1") (class "Default")
      (node (ref "IC9") (pin "B2") (pinfunction "SW1_1_B2") (pintype "bidirectional"))
      (node (ref "IC9") (pin "B3") (pinfunction "SW1_2_B3") (pintype "bidirectional"))
      (node (ref "L7") (pin "1") (pinfunction "1_1") (pintype "bidirectional"))
    )
    (net (code "20") (name "LX2") (class "Default")
      (node (ref "IC9") (pin "D2") (pinfunction "SW2_1_D2") (pintype "bidirectional"))
      (node (ref "IC9") (pin "D3") (pinfunction "SW2_2_D3") (pintype "bidirectional"))
      (node (ref "L7") (pin "2") (pinfunction "2_2") (pintype "bidirectional"))
    )
    (net (code "21") (name "MOSI") (class "Default")
      (node (ref "J1") (pin "14") (pinfunction "14_14") (pintype "bidirectional"))
      (node (ref "U1") (pin "P$B13") (pinfunction "P0.03/AIN1_P$B13") (pintype "bidirectional"))
    )
    (net (code "22") (name "Net-(ANT1-FEED)") (class "Default")
      (node (ref "ANT1") (pin "1") (pinfunction "FEED_1") (pintype "input"))
      (node (ref "C22") (pin "1") (pinfunction "1_1") (pintype "passive"))
      (node (ref "C4") (pin "1") (pinfunction "1_1") (pintype "passive"))
      (node (ref "L1") (pin "2") (pinfunction "2_2") (pintype "passive"))
    )
    (net (code "23") (name "Net-(D2-K)") (class "Default")
      (node (ref "C2-EP-DR") (pin "1") (pinfunction "1_1") (pintype "passive"))
      (node (ref "D2") (pin "1") (pinfunction "K_1") (pintype "bidirectional"))
      (node (ref "D4") (pin "2") (pinfunction "A_2") (pintype "bidirectional"))
    )
    (net (code "24") (name "Net-(D5-A)") (class "Default")
      (node (ref "C2-EP-DR") (pin "2") (pinfunction "2_2") (pintype "passive"))
      (node (ref "D5") (pin "2") (pinfunction "A_2") (pintype "bidirectional"))
      (node (ref "L5") (pin "1") (pinfunction "1_1") (pintype "passive"))
      (node (ref "Q3") (pin "3") (pinfunction "D_3") (pintype "bidirectional"))
    )
    (net (code "25") (name "Net-(EPD_C1-Pad2)") (class "Default")
      (node (ref "EPD_C1") (pin "2") (pinfunction "2_2") (pintype "passive"))
      (node (ref "J1") (pin "5") (pinfunction "5_5") (pintype "bidirectional"))
    )
    (net (code "26") (name "Net-(EPD_C2-Pad2)") (class "Default")
      (node (ref "EPD_C2") (pin "2") (pinfunction "2_2") (pintype "passive"))
      (node (ref "J1") (pin "4") (pinfunction "4_4") (pintype "bidirectional"))
    )
    (net (code "27") (name "Net-(EPD_C6-Pad2)") (class "Default")
      (node (ref "EPD_C6") (pin "2") (pinfunction "2_2") (pintype "passive"))
      (node (ref "J1") (pin "18") (pinfunction "18_18") (pintype "bidirectional"))
    )
    (net (code "28") (name "Net-(EPD_C7-Pad2)") (class "Default")
      (node (ref "EPD_C7") (pin "2") (pinfunction "2_2") (pintype "passive"))
      (node (ref "J1") (pin "19") (pinfunction "19_19") (pintype "bidirectional"))
    )
    (net (code "29") (name "Net-(EPD_C8-Pad2)") (class "Default")
      (node (ref "EPD_C8") (pin "2") (pinfunction "2_2") (pintype "passive"))
      (node (ref "J1") (pin "20") (pinfunction "20_20") (pintype "bidirectional"))
    )
    (net (code "30") (name "Net-(EPD_C10-Pad2)") (class "Default")
      (node (ref "EPD_C10") (pin "2") (pinfunction "2_2") (pintype "passive"))
      (node (ref "J1") (pin "22") (pinfunction "22_22") (pintype "bidirectional"))
    )
    (net (code "31") (name "Net-(EPD_C12-Pad2)") (class "Default")
      (node (ref "EPD_C12") (pin "2") (pinfunction "2_2") (pintype "passive"))
      (node (ref "J1") (pin "24") (pinfunction "24_24") (pintype "bidirectional"))
    )
    (net (code "32") (name "Net-(IC1-TS{slash}MR)") (class "Default")
      (node (ref "IC1") (pin "D1") (pinfunction "TS/MR_D1") (pintype "bidirectional"))
      (node (ref "R9") (pin "2") (pinfunction "2_2") (pintype "bidirectional"))
    )
    (net (code "33") (name "Net-(IC2-REG)") (class "Default")
      (node (ref "C32") (pin "2") (pinfunction "2_2") (pintype "passive"))
      (node (ref "IC2") (pin "A2") (pinfunction "REG_A2") (pintype "bidirectional"))
    )
    (net (code "34") (name "Net-(IC3-SDO)") (class "Default")
      (node (ref "IC3") (pin "1") (pinfunction "SDO_1") (pintype "bidirectional"))
      (node (ref "R3") (pin "2") (pinfunction "2_2") (pintype "bidirectional"))
    )
    (net (code "35") (name "Net-(IC9-SCL)") (class "Default")
      (node (ref "IC9") (pin "D1") (pinfunction "SCL_D1") (pintype "bidirectional"))
      (node (ref "R4") (pin "2") (pinfunction "2_2") (pintype "bidirectional"))
    )
    (net (code "36") (name "Net-(IC9-SDA)") (class "Default")
      (node (ref "IC9") (pin "E1") (pinfunction "SDA_E1") (pintype "bidirectional"))
      (node (ref "R2") (pin "2") (pinfunction "2_2") (pintype "bidirectional"))
    )
    (net (code "37") (name "Net-(J4-CC1)") (class "Default")
      (node (ref "J4") (pin "A5") (pinfunction "CC1_A5") (pintype "bidirectional"))
      (node (ref "R1_USB") (pin "2") (pinfunction "2_2") (pintype "bidirectional"))
    )
    (net (code "38") (name "Net-(J4-CC2)") (class "Default")
      (node (ref "J4") (pin "B5") (pinfunction "CC2_B5") (pintype "bidirectional"))
      (node (ref "R2_USB") (pin "1") (pinfunction "1_1") (pintype "bidirectional"))
    )
    (net (code "39") (name "Net-(L2-Pad2)") (class "Default")
      (node (ref "L2") (pin "2") (pinfunction "2_2") (pintype "passive"))
      (node (ref "L3") (pin "1") (pinfunction "1_1") (pintype "passive"))
    )
    (net (code "40") (name "Net-(R1_EP_DR-Pad1)") (class "Default")
      (node (ref "R1_EP_DR") (pin "1") (pinfunction "1_1") (pintype "bidirectional"))
      (node (ref "R_TYPE_SEL") (pin "2") (pinfunction "2_2") (pintype "bidirectional"))
      (node (ref "SJ1") (pin "2") (pinfunction "2_2") (pintype "passive"))
    )
    (net (code "41") (name "Net-(U1-ANT)") (class "Default")
      (node (ref "C3") (pin "1") (pinfunction "1_1") (pintype "passive"))
      (node (ref "L1") (pin "1") (pinfunction "1_1") (pintype "passive"))
      (node (ref "U1") (pin "P$H23") (pinfunction "ANT_P$H23") (pintype "bidirectional"))
    )
    (net (code "42") (name "Net-(U1-DCC)") (class "Default")
      (node (ref "L2") (pin "1") (pinfunction "1_1") (pintype "passive"))
      (node (ref "U1") (pin "P$B3") (pinfunction "DCC_P$B3") (pintype "output"))
    )
    (net (code "43") (name "Net-(U1-DEC1)") (class "Default")
      (node (ref "C5") (pin "1") (pinfunction "1_1") (pintype "passive"))
      (node (ref "U1") (pin "P$C1") (pinfunction "DEC1_P$C1") (pintype "power_in"))
    )
    (net (code "44") (name "Net-(U1-DEC2)") (class "Default")
      (node (ref "C13") (pin "1") (pinfunction "1_1") (pintype "passive"))
      (node (ref "U1") (pin "P$A18") (pinfunction "DEC2_P$A18") (pintype "bidirectional"))
    )
    (net (code "45") (name "Net-(U1-DEC3V3)") (class "Default")
      (node (ref "C20") (pin "1") (pinfunction "1_1") (pintype "passive"))
      (node (ref "U1") (pin "P$AC5") (pinfunction "DEC3V3_P$AC5") (pintype "bidirectional"))
    )
    (net (code "46") (name "Net-(U1-DEC5)") (class "Default")
      (node (ref "C9") (pin "1") (pinfunction "1_1") (pintype "passive"))
      (node (ref "U1") (pin "P$N24") (pinfunction "DEC5_P$N24") (pintype "bidirectional"))
    )
    (net (code "47") (name "Net-(U1-XC1)") (class "Default")
      (node (ref "C1") (pin "1") (pinfunction "1_1") (pintype "passive"))
      (node (ref "U1") (pin "P$B24") (pinfunction "XC1_P$B24") (pintype "input"))
      (node (ref "X1") (pin "1") (pinfunction "1_1") (pintype "passive"))
    )
    (net (code "48") (name "Net-(U1-XC2)") (class "Default")
      (node (ref "C2") (pin "1") (pinfunction "1_1") (pintype "passive"))
      (node (ref "U1") (pin "P$A23") (pinfunction "XC2_P$A23") (pintype "output"))
      (node (ref "X1") (pin "3") (pinfunction "3_3") (pintype "passive"))
    )
    (net (code "49") (name "OUT+") (class "Default")
      (node (ref "IC2") (pin "A3") (pinfunction "OUT+_A3") (pintype "bidirectional"))
      (node (ref "TP_OP") (pin "TP") (pinfunction "TP_TP") (pintype "input"))
    )
    (net (code "50") (name "OUT-") (class "Default")
      (node (ref "IC2") (pin "C3") (pinfunction "OUT-_C3") (pintype "bidirectional"))
      (node (ref "TP_ON") (pin "TP") (pinfunction "TP_TP") (pintype "input"))
    )
    (net (code "51") (name "P0.00") (class "Default")
      (node (ref "C17") (pin "2") (pinfunction "2_2") (pintype "passive"))
      (node (ref "U1") (pin "P$D2") (pinfunction "P0.00/XL1_P$D2") (pintype "bidirectional"))
      (node (ref "X2") (pin "1") (pinfunction "1_1") (pintype "passive"))
    )
    (net (code "52") (name "P0.01") (class "Default")
      (node (ref "C18") (pin "2") (pinfunction "2_2") (pintype "passive"))
      (node (ref "U1") (pin "P$F2") (pinfunction "P0.01/XL2_P$F2") (pintype "bidirectional"))
      (node (ref "X2") (pin "2") (pinfunction "2_2") (pintype "passive"))
    )
    (net (code "53") (name "P0.04") (class "Default")
      (node (ref "U1") (pin "P$J1") (pinfunction "P0.04/AIN2_P$J1") (pintype "bidirectional"))
    )
    (net (code "54") (name "P0.09") (class "Default")
      (node (ref "U1") (pin "P$L24") (pinfunction "P0.09/NFC1_P$L24") (pintype "bidirectional"))
    )
    (net (code "55") (name "P0.13") (class "Default")
      (node (ref "C30") (pin "2") (pinfunction "2_2") (pintype "passive"))
      (node (ref "R5") (pin "1") (pinfunction "1_1") (pintype "bidirectional"))
      (node (ref "SW_UP") (pin "2") (pinfunction "2_2") (pintype "passive"))
      (node (ref "U1") (pin "P$AD8") (pinfunction "P0.13_P$AD8") (pintype "bidirectional"))
    )
    (net (code "56") (name "P0.14") (class "Default")
      (node (ref "C31") (pin "2") (pinfunction "2_2") (pintype "passive"))
      (node (ref "R8") (pin "1") (pinfunction "1_1") (pintype "bidirectional"))
      (node (ref "SW_ENT") (pin "2") (pinfunction "2_2") (pintype "passive"))
      (node (ref "U1") (pin "P$AC9") (pinfunction "P0.14_P$AC9") (pintype "bidirectional"))
    )
    (net (code "57") (name "P0.19") (class "Default")
      (node (ref "U1") (pin "P$AC15") (pinfunction "P0.19_P$AC15") (pintype "bidirectional"))
    )
    (net (code "58") (name "P0.20") (class "Default")
      (node (ref "U1") (pin "P$AD16") (pinfunction "P0.20_P$AD16") (pintype "bidirectional"))
    )
    (net (code "59") (name "P0.21") (class "Default")
      (node (ref "U1") (pin "P$AC17") (pinfunction "P0.21_P$AC17") (pintype "bidirectional"))
    )
    (net (code "60") (name "P0.22") (class "Default")
      (node (ref "U1") (pin "P$AD18") (pinfunction "P0.22_P$AD18") (pintype "bidirectional"))
    )
    (net (code "61") (name "P0.23") (class "Default")
      (node (ref "U1") (pin "P$AC19") (pinfunction "P0.23_P$AC19") (pintype "bidirectional"))
    )
    (net (code "62") (name "P0.24") (class "Default")
      (node (ref "U1") (pin "P$AD20") (pinfunction "P0.24_P$AD20") (pintype "bidirectional"))
    )
    (net (code "63") (name "P0.25") (class "Default")
      (node (ref "U1") (pin "P$AC21") (pinfunction "P0.25_P$AC21") (pintype "bidirectional"))
    )
    (net (code "64") (name "P0.26") (class "Default")
      (node (ref "U1") (pin "P$G1") (pinfunction "P0.26_P$G1") (pintype "bidirectional"))
    )
    (net (code "65") (name "P0.27") (class "Default")
      (node (ref "U1") (pin "P$H2") (pinfunction "P0.27_P$H2") (pintype "bidirectional"))
    )
    (net (code "66") (name "P0.28") (class "Default")
      (node (ref "U1") (pin "P$B11") (pinfunction "P0.28/AIN4_P$B11") (pintype "bidirectional"))
    )
    (net (code "67") (name "P0.29") (class "Default")
      (node (ref "U1") (pin "P$A10") (pinfunction "P0.29/AIN5_P$A10") (pintype "bidirectional"))
    )
    (net (code "68") (name "P0.30") (class "Default")
      (node (ref "U1") (pin "P$B9") (pinfunction "P0.30/AIN6_P$B9") (pintype "bidirectional"))
    )
    (net (code "69") (name "P0.31") (class "Default")
      (node (ref "U1") (pin "P$A8") (pinfunction "P0.31/AIN7_P$A8") (pintype "bidirectional"))
    )
    (net (code "70") (name "P1.01") (class "Default")
      (node (ref "Q1") (pin "1") (pinfunction "G_1") (pintype "bidirectional"))
      (node (ref "R_PWR_EPD") (pin "1") (pinfunction "1_1") (pintype "bidirectional"))
      (node (ref "U1") (pin "P$Y23") (pinfunction "P1.01_P$Y23") (pintype "bidirectional"))
    )
    (net (code "71") (name "P1.02") (class "Default")
      (node (ref "C29") (pin "2") (pinfunction "2_2") (pintype "passive"))
      (node (ref "R7") (pin "1") (pinfunction "1_1") (pintype "bidirectional"))
      (node (ref "SW_DN") (pin "2") (pinfunction "2_2") (pintype "passive"))
      (node (ref "U1") (pin "P$W24") (pinfunction "P1.02_P$W24") (pintype "bidirectional"))
    )
    (net (code "72") (name "P1.03") (class "Default")
      (node (ref "U1") (pin "P$V23") (pinfunction "P1.03_P$V23") (pintype "bidirectional"))
    )
    (net (code "73") (name "P1.04") (class "Default")
      (node (ref "U1") (pin "P$U24") (pinfunction "P1.04_P$U24") (pintype "bidirectional"))
    )
    (net (code "74") (name "P1.05") (class "Default")
      (node (ref "U1") (pin "P$T23") (pinfunction "P1.05_P$T23") (pintype "bidirectional"))
    )
    (net (code "75") (name "P1.06") (class "Default")
      (node (ref "U1") (pin "P$R24") (pinfunction "P1.06_P$R24") (pintype "bidirectional"))
    )
    (net (code "76") (name "P1.07") (class "Default")
      (node (ref "U1") (pin "P$P23") (pinfunction "P1.07_P$P23") (pintype "bidirectional"))
    )
    (net (code "77") (name "P1.09") (class "Default")
      (node (ref "U1") (pin "P$R1") (pinfunction "P1.09_P$R1") (pintype "bidirectional"))
    )
    (net (code "78") (name "P1.10") (class "Default")
      (node (ref "U1") (pin "P$A20") (pinfunction "P1.10_P$A20") (pintype "bidirectional"))
    )
    (net (code "79") (name "P1.11") (class "Default")
      (node (ref "U1") (pin "P$B19") (pinfunction "P1.11_P$B19") (pintype "bidirectional"))
    )
    (net (code "80") (name "P1.12") (class "Default")
      (node (ref "U1") (pin "P$B17") (pinfunction "P1.12_P$B17") (pintype "bidirectional"))
    )
    (net (code "81") (name "P1.13") (class "Default")
      (node (ref "U1") (pin "P$A16") (pinfunction "P1.13_P$A16") (pintype "bidirectional"))
    )
    (net (code "82") (name "P1.14") (class "Default")
      (node (ref "U1") (pin "P$B15") (pinfunction "P1.14_P$B15") (pintype "bidirectional"))
    )
    (net (code "83") (name "P1.15") (class "Default")
      (node (ref "U1") (pin "P$A14") (pinfunction "P1.15_P$A14") (pintype "bidirectional"))
    )
    (net (code "84") (name "PMIC_INT") (class "Default")
      (node (ref "IC1") (pin "A1") (pinfunction "~{INT}_A1") (pintype "bidirectional"))
      (node (ref "U1") (pin "P$T2") (pinfunction "P0.11_P$T2") (pintype "bidirectional"))
    )
    (net (code "85") (name "PREVGH") (class "Default")
      (node (ref "D5") (pin "1") (pinfunction "K_1") (pintype "bidirectional"))
      (node (ref "EPD_C9") (pin "2") (pinfunction "2_2") (pintype "passive"))
      (node (ref "J1") (pin "21") (pinfunction "21_21") (pintype "bidirectional"))
    )
    (net (code "86") (name "PREVGL") (class "Default")
      (node (ref "D2") (pin "2") (pinfunction "A_2") (pintype "bidirectional"))
      (node (ref "EPD_C11") (pin "2") (pinfunction "2_2") (pintype "passive"))
      (node (ref "J1") (pin "23") (pinfunction "23_23") (pintype "bidirectional"))
    )
    (net (code "87") (name "RESE") (class "Default")
      (node (ref "J1") (pin "3") (pinfunction "3_3") (pintype "bidirectional"))
      (node (ref "Q3") (pin "2") (pinfunction "S_2") (pintype "bidirectional"))
      (node (ref "R1_EP_DR") (pin "2") (pinfunction "2_2") (pintype "bidirectional"))
    )
    (net (code "88") (name "RESET") (class "Default")
      (node (ref "J2") (pin "6") (pinfunction "6_6") (pintype "bidirectional"))
      (node (ref "TP_RESET") (pin "TP") (pinfunction "TP_TP") (pintype "input"))
      (node (ref "U1") (pin "P$AC13") (pinfunction "P0.18/RESET_P$AC13") (pintype "bidirectional"))
    )
    (net (code "89") (name "SCK") (class "Default")
      (node (ref "J1") (pin "13") (pinfunction "13_13") (pintype "bidirectional"))
      (node (ref "U1") (pin "P$A12") (pinfunction "P0.02/AIN0_P$A12") (pintype "bidirectional"))
    )
    (net (code "90") (name "SCL") (class "Default")
      (node (ref "IC1") (pin "B1") (pinfunction "SCL_B1") (pintype "bidirectional"))
      (node (ref "IC2") (pin "C1") (pinfunction "SCL_C1") (pintype "bidirectional"))
      (node (ref "IC3") (pin "12") (pinfunction "SCX_12") (pintype "bidirectional"))
      (node (ref "R17") (pin "2") (pinfunction "2_2") (pintype "bidirectional"))
      (node (ref "R4") (pin "1") (pinfunction "1_1") (pintype "bidirectional"))
      (node (ref "TP_SCL") (pin "TP") (pinfunction "TP_TP") (pintype "input"))
      (node (ref "U1") (pin "P$M2") (pinfunction "P0.07_P$M2") (pintype "bidirectional"))
      (node (ref "U3") (pin "7") (pinfunction "SCL_7") (pintype "input"))
    )
    (net (code "91") (name "SDA") (class "Default")
      (node (ref "IC1") (pin "C1") (pinfunction "SDA_C1") (pintype "bidirectional"))
      (node (ref "IC2") (pin "B2") (pinfunction "SDA_B2") (pintype "bidirectional"))
      (node (ref "IC3") (pin "2") (pinfunction "SDX_2") (pintype "bidirectional"))
      (node (ref "R18") (pin "2") (pinfunction "2_2") (pintype "bidirectional"))
      (node (ref "R2") (pin "1") (pinfunction "1_1") (pintype "bidirectional"))
      (node (ref "TP_SDA") (pin "TP") (pinfunction "TP_TP") (pintype "input"))
      (node (ref "U1") (pin "P$L1") (pinfunction "P0.06_P$L1") (pintype "bidirectional"))
      (node (ref "U3") (pin "8") (pinfunction "SDA_8") (pintype "bidirectional"))
    )
    (net (code "92") (name "SWDCLK") (class "Default")
      (node (ref "J2") (pin "4") (pinfunction "4_4") (pintype "bidirectional"))
      (node (ref "TP_SWDCLK") (pin "TP") (pinfunction "TP_TP") (pintype "input"))
      (node (ref "U1") (pin "P$AA24") (pinfunction "SWDCLK_P$AA24") (pintype "input"))
    )
    (net (code "93") (name "SWDIO") (class "Default")
      (node (ref "J2") (pin "2") (pinfunction "2_2") (pintype "bidirectional"))
      (node (ref "TP_SWDIO") (pin "TP") (pinfunction "TP_TP") (pintype "input"))
      (node (ref "U1") (pin "P$AC24") (pinfunction "SWDIO_P$AC24") (pintype "bidirectional"))
    )
    (net (code "94") (name "SWO") (class "Default")
      (node (ref "TP_SWO") (pin "TP") (pinfunction "TP_TP") (pintype "input"))
      (node (ref "U1") (pin "P$AD22") (pinfunction "P1.00_P$AD22") (pintype "bidirectional"))
    )
    (net (code "95") (name "VBAT") (class "Default")
      (node (ref "C27") (pin "2") (pinfunction "2_2") (pintype "passive"))
      (node (ref "C37") (pin "2") (pinfunction "2_2") (pintype "passive"))
      (node (ref "IC1") (pin "C2") (pinfunction "BAT_C2") (pintype "bidirectional"))
      (node (ref "TP_VBAT") (pin "TP") (pinfunction "TP_TP") (pintype "input"))
      (node (ref "U3") (pin "2") (pinfunction "CELL_2") (pintype "power_in"))
      (node (ref "U3") (pin "3") (pinfunction "VDD_3") (pintype "power_in"))
    )
    (net (code "96") (name "VBUS") (class "Default")
      (node (ref "C21") (pin "1") (pinfunction "1_1") (pintype "passive"))
      (node (ref "C38") (pin "2") (pinfunction "2_2") (pintype "passive"))
      (node (ref "C42") (pin "2") (pinfunction "2_2") (pintype "passive"))
      (node (ref "C43") (pin "1") (pinfunction "1_1") (pintype "passive"))
      (node (ref "D3") (pin "5") (pinfunction "VBUS_5") (pintype "bidirectional"))
      (node (ref "IC1") (pin "A2") (pinfunction "IN_A2") (pintype "bidirectional"))
      (node (ref "J4") (pin "A4_B9") (pinfunction "VBUS_A4_B9") (pintype "power_in"))
      (node (ref "J4") (pin "A9_B4") (pinfunction "VBUS_A9_B4") (pintype "power_in"))
      (node (ref "U1") (pin "P$AD2") (pinfunction "VBUS_P$AD2") (pintype "power_in"))
    )
    (net (code "97") (name "VREG") (class "Default")
      (node (ref "C23") (pin "2") (pinfunction "2_2") (pintype "passive"))
      (node (ref "C24") (pin "2") (pinfunction "2_2") (pintype "passive"))
      (node (ref "C39") (pin "1") (pinfunction "1_1") (pintype "passive"))
      (node (ref "IC1") (pin "B2") (pinfunction "SYS_B2") (pintype "bidirectional"))
      (node (ref "IC9") (pin "A1") (pinfunction "EN_A1") (pintype "bidirectional"))
      (node (ref "IC9") (pin "A2") (pinfunction "VIN_1_A2") (pintype "bidirectional"))
      (node (ref "IC9") (pin "A3") (pinfunction "VIN_2_A3") (pintype "bidirectional"))
      (node (ref "TP_VREG") (pin "TP") (pinfunction "TP_TP") (pintype "input"))
    )
    (net (code "98") (name "unconnected-(ANT1-NC-Pad2)") (class "Default")
      (node (ref "ANT1") (pin "2") (pinfunction "NC_2") (pintype "no_connect"))
    )
    (net (code "99") (name "unconnected-(C33-Pad1)") (class "Default")
      (node (ref "C33") (pin "1") (pinfunction "1_1") (pintype "passive"))
    )
    (net (code "100") (name "unconnected-(IC3-ASCL-Pad11)") (class "Default")
      (node (ref "IC3") (pin "11") (pinfunction "ASCL_11") (pintype "bidirectional"))
    )
    (net (code "101") (name "unconnected-(IC3-ASDA-Pad4)") (class "Default")
      (node (ref "IC3") (pin "4") (pinfunction "ASDA_4") (pintype "bidirectional"))
    )
    (net (code "102") (name "unconnected-(J1-Pad1)") (class "Default")
      (node (ref "J1") (pin "1") (pinfunction "1_1") (pintype "bidirectional"))
    )
    (net (code "103") (name "unconnected-(J1-Pad6)") (class "Default")
      (node (ref "J1") (pin "6") (pinfunction "6_6") (pintype "bidirectional"))
    )
    (net (code "104") (name "unconnected-(J1-Pad7)") (class "Default")
      (node (ref "J1") (pin "7") (pinfunction "7_7") (pintype "bidirectional"))
    )
    (net (code "105") (name "unconnected-(J4-SBU1-PadA8)") (class "Default")
      (node (ref "J4") (pin "A8") (pinfunction "SBU1_A8") (pintype "bidirectional"))
    )
    (net (code "106") (name "unconnected-(J4-SBU2-PadB8)") (class "Default")
      (node (ref "J4") (pin "B8") (pinfunction "SBU2_B8") (pintype "bidirectional"))
    )
    (net (code "107") (name "unconnected-(U1-DCCH-PadP$AB2)") (class "Default")
      (node (ref "U1") (pin "P$AB2") (pinfunction "DCCH_P$AB2") (pintype "bidirectional"))
    )
  )
)
